# PLC.net
KiCad netlist of a schematic drawn in EAGLE
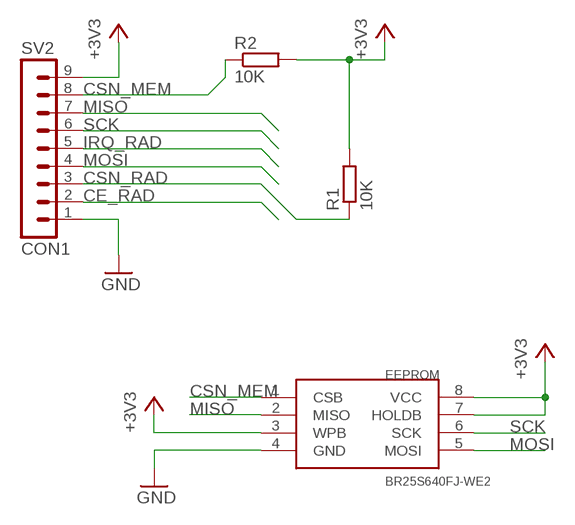
[diagram p0: schematic, sheet 1]

(export (version "E")
  (design (tool "Eeschema 10.0.6"))
  (components
    (comp (ref "EEPROM")
      (value "BR25S640FJ-WE2")
      (footprint "eagle-import:SO8")
      (libsource (lib "eagle-import") (part "BR25S640FJ-WE2"))
    )
    (comp (ref "R1")
      (value "10K")
      (footprint "eagle-import:R1206")
      (libsource (lib "eagle-import") (part "R-EU_R1206"))
    )
    (comp (ref "R2")
      (value "10K")
      (footprint "eagle-import:R1206")
      (libsource (lib "eagle-import") (part "R-EU_R1206"))
    )
    (comp (ref "SV2")
      (value "CON1")
      (footprint "eagle-import:MA09-1W")
      (libsource (lib "eagle-import") (part "MA09-1W"))
    )
  )
  (nets
    (net (code "1") (name "+3V3") (class "Default")
      (node (ref "EEPROM") (pin "3") (pinfunction "WPB_3") (pintype "bidirectional"))
      (node (ref "EEPROM") (pin "7") (pinfunction "HOLDB_7") (pintype "bidirectional"))
      (node (ref "EEPROM") (pin "8") (pinfunction "VCC_8") (pintype "bidirectional"))
      (node (ref "R1") (pin "2") (pinfunction "2_2") (pintype "passive"))
      (node (ref "R2") (pin "2") (pinfunction "2_2") (pintype "passive"))
      (node (ref "SV2") (pin "9") (pinfunction "9_9") (pintype "passive"))
    )
    (net (code "2") (name "/CE_RAD") (class "Default")
      (node (ref "SV2") (pin "2") (pinfunction "2_2") (pintype "passive"))
    )
    (net (code "3") (name "/CSN_MEM") (class "Default")
      (node (ref "EEPROM") (pin "1") (pinfunction "CSB_1") (pintype "bidirectional"))
      (node (ref "R2") (pin "1") (pinfunction "1_1") (pintype "passive"))
      (node (ref "SV2") (pin "8") (pinfunction "8_8") (pintype "passive"))
    )
    (net (code "4") (name "/CSN_RAD") (class "Default")
      (node (ref "R1") (pin "1") (pinfunction "1_1") (pintype "passive"))
      (node (ref "SV2") (pin "3") (pinfunction "3_3") (pintype "passive"))
    )
    (net (code "5") (name "/IRQ_RAD") (class "Default")
      (node (ref "SV2") (pin "5") (pinfunction "5_5") (pintype "passive"))
    )
    (net (code "6") (name "/MISO") (class "Default")
      (node (ref "EEPROM") (pin "2") (pinfunction "MISO_2") (pintype "bidirectional"))
      (node (ref "SV2") (pin "7") (pinfunction "7_7") (pintype "passive"))
    )
    (net (code "7") (name "/MOSI") (class "Default")
      (node (ref "EEPROM") (pin "5") (pinfunction "MOSI_5") (pintype "bidirectional"))
      (node (ref "SV2") (pin "4") (pinfunction "4_4") (pintype "passive"))
    )
    (net (code "8") (name "/SCK") (class "Default")
      (node (ref "EEPROM") (pin "6") (pinfunction "SCK_6") (pintype "bidirectional"))
      (node (ref "SV2") (pin "6") (pinfunction "6_6") (pintype "passive"))
    )
    (net (code "9") (name "GND") (class "Default")
      (node (ref "EEPROM") (pin "4") (pinfunction "GND_4") (pintype "bidirectional"))
      (node (ref "SV2") (pin "1") (pinfunction "1_1") (pintype "passive"))
    )
  )
)
